# Master.net
KiCad netlist of a schematic drawn in EAGLE
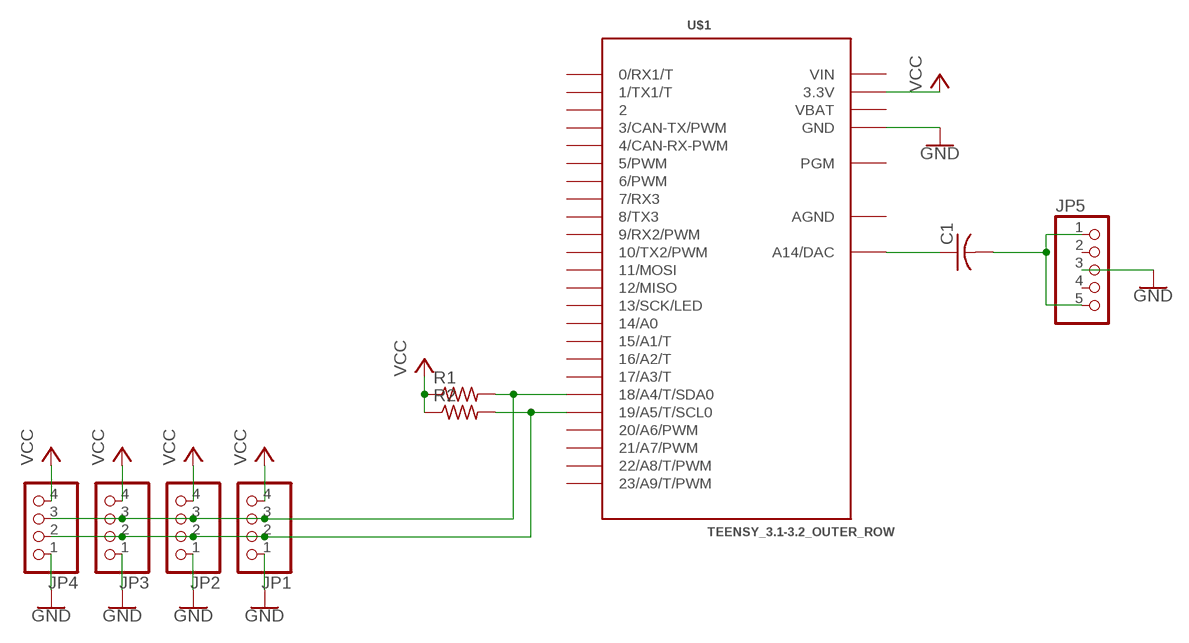
[diagram p0: schematic, sheet 1]

(export (version "E")
  (design (tool "Eeschema 10.0.6"))
  (components
    (comp (ref "C1")
      (value "C-US025-030X050")
      (footprint "eagle-import:C025-030X050")
      (libsource (lib "eagle-import") (part "C-US025-030X050"))
    )
    (comp (ref "JP1")
      (value "PINHD-1X4")
      (footprint "eagle-import:1X04")
      (libsource (lib "eagle-import") (part "PINHD-1X4"))
    )
    (comp (ref "JP2")
      (value "PINHD-1X4")
      (footprint "eagle-import:1X04")
      (libsource (lib "eagle-import") (part "PINHD-1X4"))
    )
    (comp (ref "JP3")
      (value "PINHD-1X4")
      (footprint "eagle-import:1X04")
      (libsource (lib "eagle-import") (part "PINHD-1X4"))
    )
    (comp (ref "JP4")
      (value "PINHD-1X4")
      (footprint "eagle-import:1X04")
      (libsource (lib "eagle-import") (part "PINHD-1X4"))
    )
    (comp (ref "JP5")
      (value "PINHD-1X5")
      (footprint "eagle-import:1X05")
      (libsource (lib "eagle-import") (part "PINHD-1X5"))
    )
    (comp (ref "R1")
      (value "R-US_0207/7")
      (footprint "eagle-import:0207_7")
      (libsource (lib "eagle-import") (part "R-US_0207/7"))
    )
    (comp (ref "R2")
      (value "R-US_0207/7")
      (footprint "eagle-import:0207_7")
      (libsource (lib "eagle-import") (part "R-US_0207/7"))
    )
    (comp (ref "U$1")
      (value "TEENSY_3.1-3.2_OUTER_ROW")
      (footprint "eagle-import:TEENSY_3.0-3.2&LC_OUTER_ROW")
      (libsource (lib "eagle-import") (part "TEENSY_3.1-3.2_OUTER_ROW"))
    )
  )
  (nets
    (net (code "1") (name "/AGND") (class "Default")
      (node (ref "U$1") (pin "AGND") (pinfunction "AGND_AGND") (pintype "power_in"))
    )
    (net (code "2") (name "/VBAT") (class "Default")
      (node (ref "U$1") (pin "VBAT") (pinfunction "VBAT_VBAT") (pintype "power_in"))
    )
    (net (code "3") (name "/VIN") (class "Default")
      (node (ref "U$1") (pin "VIN") (pinfunction "VIN_VIN") (pintype "power_in"))
    )
    (net (code "4") (name "GND") (class "Default")
      (node (ref "JP1") (pin "1") (pinfunction "1_1") (pintype "passive"))
      (node (ref "JP2") (pin "1") (pinfunction "1_1") (pintype "passive"))
      (node (ref "JP3") (pin "1") (pinfunction "1_1") (pintype "passive"))
      (node (ref "JP4") (pin "1") (pinfunction "1_1") (pintype "passive"))
      (node (ref "JP5") (pin "3") (pinfunction "3_3") (pintype "passive"))
      (node (ref "U$1") (pin "GND") (pinfunction "GND_GND") (pintype "power_in"))
      (node (ref "U$1") (pin "GND1") (pinfunction "GND_GND1") (pintype "power_in"))
    )
    (net (code "5") (name "Net-(C1-Pad2)") (class "Default")
      (node (ref "C1") (pin "2") (pinfunction "2_2") (pintype "passive"))
      (node (ref "JP5") (pin "1") (pinfunction "1_1") (pintype "passive"))
      (node (ref "JP5") (pin "5") (pinfunction "5_5") (pintype "passive"))
    )
    (net (code "6") (name "Net-(U$1-18{slash}A4{slash}T{slash}SDA0)") (class "Default")
      (node (ref "JP1") (pin "3") (pinfunction "3_3") (pintype "passive"))
      (node (ref "JP2") (pin "3") (pinfunction "3_3") (pintype "passive"))
      (node (ref "JP3") (pin "3") (pinfunction "3_3") (pintype "passive"))
      (node (ref "JP4") (pin "3") (pinfunction "3_3") (pintype "passive"))
      (node (ref "R1") (pin "2") (pinfunction "2_2") (pintype "passive"))
      (node (ref "U$1") (pin "18/A4") (pinfunction "18/A4/T/SDA0_18/A4") (pintype "bidirectional"))
    )
    (net (code "7") (name "Net-(U$1-19{slash}A5{slash}T{slash}SCL0)") (class "Default")
      (node (ref "JP1") (pin "2") (pinfunction "2_2") (pintype "passive"))
      (node (ref "JP2") (pin "2") (pinfunction "2_2") (pintype "passive"))
      (node (ref "JP3") (pin "2") (pinfunction "2_2") (pintype "passive"))
      (node (ref "JP4") (pin "2") (pinfunction "2_2") (pintype "passive"))
      (node (ref "R2") (pin "2") (pinfunction "2_2") (pintype "passive"))
      (node (ref "U$1") (pin "19/A5") (pinfunction "19/A5/T/SCL0_19/A5") (pintype "bidirectional"))
    )
    (net (code "8") (name "Net-(U$1-A14{slash}DAC)") (class "Default")
      (node (ref "C1") (pin "1") (pinfunction "1_1") (pintype "passive"))
      (node (ref "U$1") (pin "RESET/DAC") (pinfunction "A14/DAC_RESET/DAC") (pintype "bidirectional"))
    )
    (net (code "9") (name "VCC") (class "Default")
      (node (ref "JP1") (pin "4") (pinfunction "4_4") (pintype "passive"))
      (node (ref "JP2") (pin "4") (pinfunction "4_4") (pintype "passive"))
      (node (ref "JP3") (pin "4") (pinfunction "4_4") (pintype "passive"))
      (node (ref "JP4") (pin "4") (pinfunction "4_4") (pintype "passive"))
      (node (ref "R1") (pin "1") (pinfunction "1_1") (pintype "passive"))
      (node (ref "R2") (pin "1") (pinfunction "1_1") (pintype "passive"))
      (node (ref "U$1") (pin "3.3V") (pinfunction "3.3V_3.3V") (pintype "power_in"))
      (node (ref "U$1") (pin "3.3V1") (pinfunction "3.3V_3.3V1") (pintype "power_in"))
    )
    (net (code "10") (name "unconnected-(JP5-Pad2)") (class "Default")
      (node (ref "JP5") (pin "2") (pinfunction "2_2") (pintype "passive"))
    )
    (net (code "11") (name "unconnected-(JP5-Pad4)") (class "Default")
      (node (ref "JP5") (pin "4") (pinfunction "4_4") (pintype "passive"))
    )
    (net (code "12") (name "unconnected-(U$1-0{slash}RX1{slash}T-Pad0)") (class "Default")
      (node (ref "U$1") (pin "0") (pinfunction "0/RX1/T_0") (pintype "bidirectional"))
    )
    (net (code "13") (name "unconnected-(U$1-1{slash}TX1{slash}T-Pad1)") (class "Default")
      (node (ref "U$1") (pin "1") (pinfunction "1/TX1/T_1") (pintype "bidirectional"))
    )
    (net (code "14") (name "unconnected-(U$1-3{slash}CAN-TX{slash}PWM-Pad3)") (class "Default")
      (node (ref "U$1") (pin "3") (pinfunction "3/CAN-TX/PWM_3") (pintype "bidirectional"))
    )
    (net (code "15") (name "unconnected-(U$1-4{slash}CAN-RX-PWM-Pad4)") (class "Default")
      (node (ref "U$1") (pin "4") (pinfunction "4/CAN-RX-PWM_4") (pintype "bidirectional"))
    )
    (net (code "16") (name "unconnected-(U$1-5{slash}PWM-Pad5)") (class "Default")
      (node (ref "U$1") (pin "5") (pinfunction "5/PWM_5") (pintype "bidirectional"))
    )
    (net (code "17") (name "unconnected-(U$1-6{slash}PWM-Pad6)") (class "Default")
      (node (ref "U$1") (pin "6") (pinfunction "6/PWM_6") (pintype "bidirectional"))
    )
    (net (code "18") (name "unconnected-(U$1-7{slash}RX3-Pad7)") (class "Default")
      (node (ref "U$1") (pin "7") (pinfunction "7/RX3_7") (pintype "bidirectional"))
    )
    (net (code "19") (name "unconnected-(U$1-8{slash}TX3-Pad8)") (class "Default")
      (node (ref "U$1") (pin "8") (pinfunction "8/TX3_8") (pintype "bidirectional"))
    )
    (net (code "20") (name "unconnected-(U$1-9{slash}RX2{slash}PWM-Pad9)") (class "Default")
      (node (ref "U$1") (pin "9") (pinfunction "9/RX2/PWM_9") (pintype "bidirectional"))
    )
    (net (code "21") (name "unconnected-(U$1-10{slash}TX2{slash}PWM-Pad10)") (class "Default")
      (node (ref "U$1") (pin "10") (pinfunction "10/TX2/PWM_10") (pintype "bidirectional"))
    )
    (net (code "22") (name "unconnected-(U$1-11{slash}MOSI-Pad11)") (class "Default")
      (node (ref "U$1") (pin "11") (pinfunction "11/MOSI_11") (pintype "bidirectional"))
    )
    (net (code "23") (name "unconnected-(U$1-12{slash}MISO-Pad12)") (class "Default")
      (node (ref "U$1") (pin "12") (pinfunction "12/MISO_12") (pintype "bidirectional"))
    )
    (net (code "24") (name "unconnected-(U$1-13{slash}SCK{slash}LED-Pad13)") (class "Default")
      (node (ref "U$1") (pin "13") (pinfunction "13/SCK/LED_13") (pintype "bidirectional"))
    )
    (net (code "25") (name "unconnected-(U$1-15{slash}A1{slash}T-Pad15{slash}A1)") (class "Default")
      (node (ref "U$1") (pin "15/A1") (pinfunction "15/A1/T_15/A1") (pintype "bidirectional"))
    )
    (net (code "26") (name "unconnected-(U$1-16{slash}A2{slash}T-Pad16{slash}A2)") (class "Default")
      (node (ref "U$1") (pin "16/A2") (pinfunction "16/A2/T_16/A2") (pintype "bidirectional"))
    )
    (net (code "27") (name "unconnected-(U$1-17{slash}A3{slash}T-Pad17{slash}A3)") (class "Default")
      (node (ref "U$1") (pin "17/A3") (pinfunction "17/A3/T_17/A3") (pintype "bidirectional"))
    )
    (net (code "28") (name "unconnected-(U$1-20{slash}A6{slash}PWM-Pad20{slash}A6)") (class "Default")
      (node (ref "U$1") (pin "20/A6") (pinfunction "20/A6/PWM_20/A6") (pintype "bidirectional"))
    )
    (net (code "29") (name "unconnected-(U$1-21{slash}A7{slash}PWM-Pad21{slash}A7)") (class "Default")
      (node (ref "U$1") (pin "21/A7") (pinfunction "21/A7/PWM_21/A7") (pintype "bidirectional"))
    )
    (net (code "30") (name "unconnected-(U$1-22{slash}A8{slash}T{slash}PWM-Pad22{slash}A8)") (class "Default")
      (node (ref "U$1") (pin "22/A8") (pinfunction "22/A8/T/PWM_22/A8") (pintype "bidirectional"))
    )
    (net (code "31") (name "unconnected-(U$1-23{slash}A9{slash}T{slash}PWM-Pad23{slash}A9)") (class "Default")
      (node (ref "U$1") (pin "23/A9") (pinfunction "23/A9/T/PWM_23/A9") (pintype "bidirectional"))
    )
    (net (code "32") (name "unconnected-(U$1-Pad2)") (class "Default")
      (node (ref "U$1") (pin "2") (pinfunction "2_2") (pintype "bidirectional"))
    )
    (net (code "33") (name "unconnected-(U$1-Pad14{slash}A0)") (class "Default")
      (node (ref "U$1") (pin "14/A0") (pinfunction "14/A0_14/A0") (pintype "bidirectional"))
    )
    (net (code "34") (name "unconnected-(U$1-PadPGM)") (class "Default")
      (node (ref "U$1") (pin "PGM") (pinfunction "PGM_PGM") (pintype "bidirectional"))
    )
  )
)
